# Power.net
KiCad netlist of a schematic drawn in Altium Designer
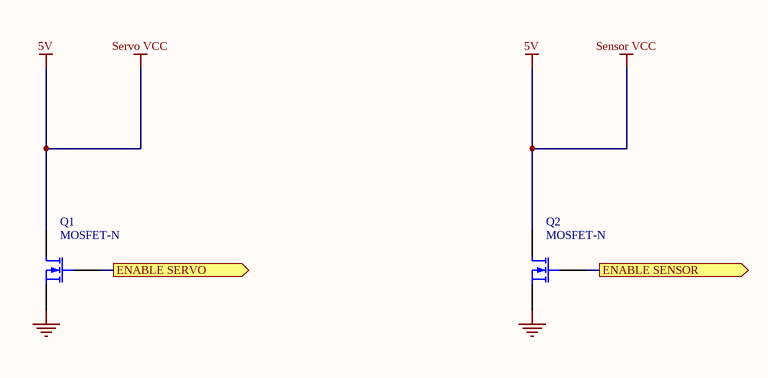
[diagram p0: Power.SchDoc]

(export (version "E")
  (design (tool "Eeschema 10.0.6"))
  (components
    (comp (ref "Q1")
      (value "MOSFET-N")
      (footprint "E3")
      (description "N-Channel MOSFET")
      (fields (field (name "PUBLISHER") "Altium Limited"))
      (libsource (lib "Miscellaneous Devices") (part "MOSFET-N"))
    )
    (comp (ref "Q2")
      (value "MOSFET-N")
      (footprint "E3")
      (description "N-Channel MOSFET")
      (fields (field (name "PUBLISHER") "Altium Limited"))
      (libsource (lib "Miscellaneous Devices") (part "MOSFET-N"))
    )
  )
  (nets
    (net (code "1") (name "/ENABLE SENSOR") (class "Default")
      (node (ref "Q2") (pin "2") (pinfunction "G_2") (pintype "passive"))
    )
    (net (code "2") (name "/ENABLE SERVO") (class "Default")
      (node (ref "Q1") (pin "2") (pinfunction "G_2") (pintype "passive"))
    )
    (net (code "3") (name "5V") (class "Default")
      (node (ref "Q1") (pin "1") (pinfunction "D_1") (pintype "passive"))
      (node (ref "Q2") (pin "1") (pinfunction "D_1") (pintype "passive"))
    )
    (net (code "4") (name "GND") (class "Default")
      (node (ref "Q1") (pin "3") (pinfunction "S_3") (pintype "passive"))
      (node (ref "Q2") (pin "3") (pinfunction "S_3") (pintype "passive"))
    )
  )
)
